# Transistor_LED.net
KiCad netlist of a schematic drawn in Altium Designer
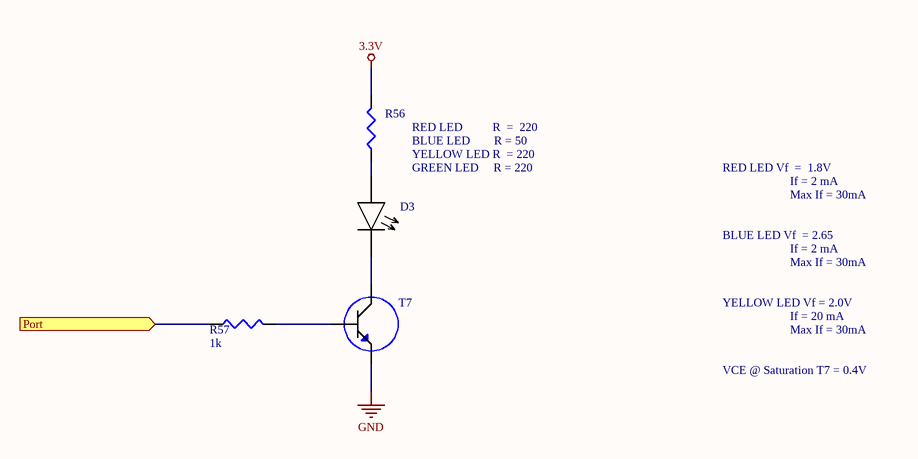
[diagram p0: Transistor_LED.SchDoc]

(export (version "E")
  (design (tool "Eeschema 10.0.6"))
  (components
    (comp (ref "D3")
      (value "LED_R")
      (footprint "0402 footprint")
      (libsource (lib "AvionicsParts") (part "LED_R"))
    )
    (comp (ref "R56")
      (value "Res3")
      (description "Resistor")
      (fields (field (name "PUBLISHER") "Altium Limited"))
      (libsource (lib "Miscellaneous Devices") (part "Res3"))
    )
    (comp (ref "R57")
      (value "1k")
      (description "Resistor")
      (fields (field (name "Comment") "Res3") (field (name "PUBLISHER") "Altium Limited"))
      (libsource (lib "Miscellaneous Devices") (part "Res3"))
    )
    (comp (ref "T7")
      (value "MMBT2222ALT1")
      (footprint "BJT")
      (description "Trans NPN 40V 0.6A SOT23")
      (fields (field (name "MF") "ON Semiconductor"))
      (libsource (lib "AvionicsParts") (part "BJT NPN"))
    )
  )
  (nets
    (net (code "1") (name "/Port") (class "Default")
      (node (ref "R57") (pin "1") (pinfunction "1_1") (pintype "passive"))
    )
    (net (code "2") (name "3.3V") (class "Default")
      (node (ref "R56") (pin "2") (pinfunction "2_2") (pintype "passive"))
    )
    (net (code "3") (name "GND") (class "Default")
      (node (ref "T7") (pin "2") (pinfunction "E_2") (pintype "passive"))
    )
    (net (code "4") (name "Net-(D3-Pad1)") (class "Default")
      (node (ref "D3") (pin "1") (pinfunction "1_1") (pintype "passive"))
      (node (ref "R56") (pin "1") (pinfunction "1_1") (pintype "passive"))
    )
    (net (code "5") (name "Net-(T7-B)") (class "Default")
      (node (ref "R57") (pin "2") (pinfunction "2_2") (pintype "passive"))
      (node (ref "T7") (pin "1") (pinfunction "B_1") (pintype "passive"))
    )
    (net (code "6") (name "Net-(T7-C)") (class "Default")
      (node (ref "D3") (pin "2") (pinfunction "2_2") (pintype "passive"))
      (node (ref "T7") (pin "3") (pinfunction "C_3") (pintype "passive"))
    )
  )
)
